# analog.net
KiCad netlist of a schematic drawn in EAGLE
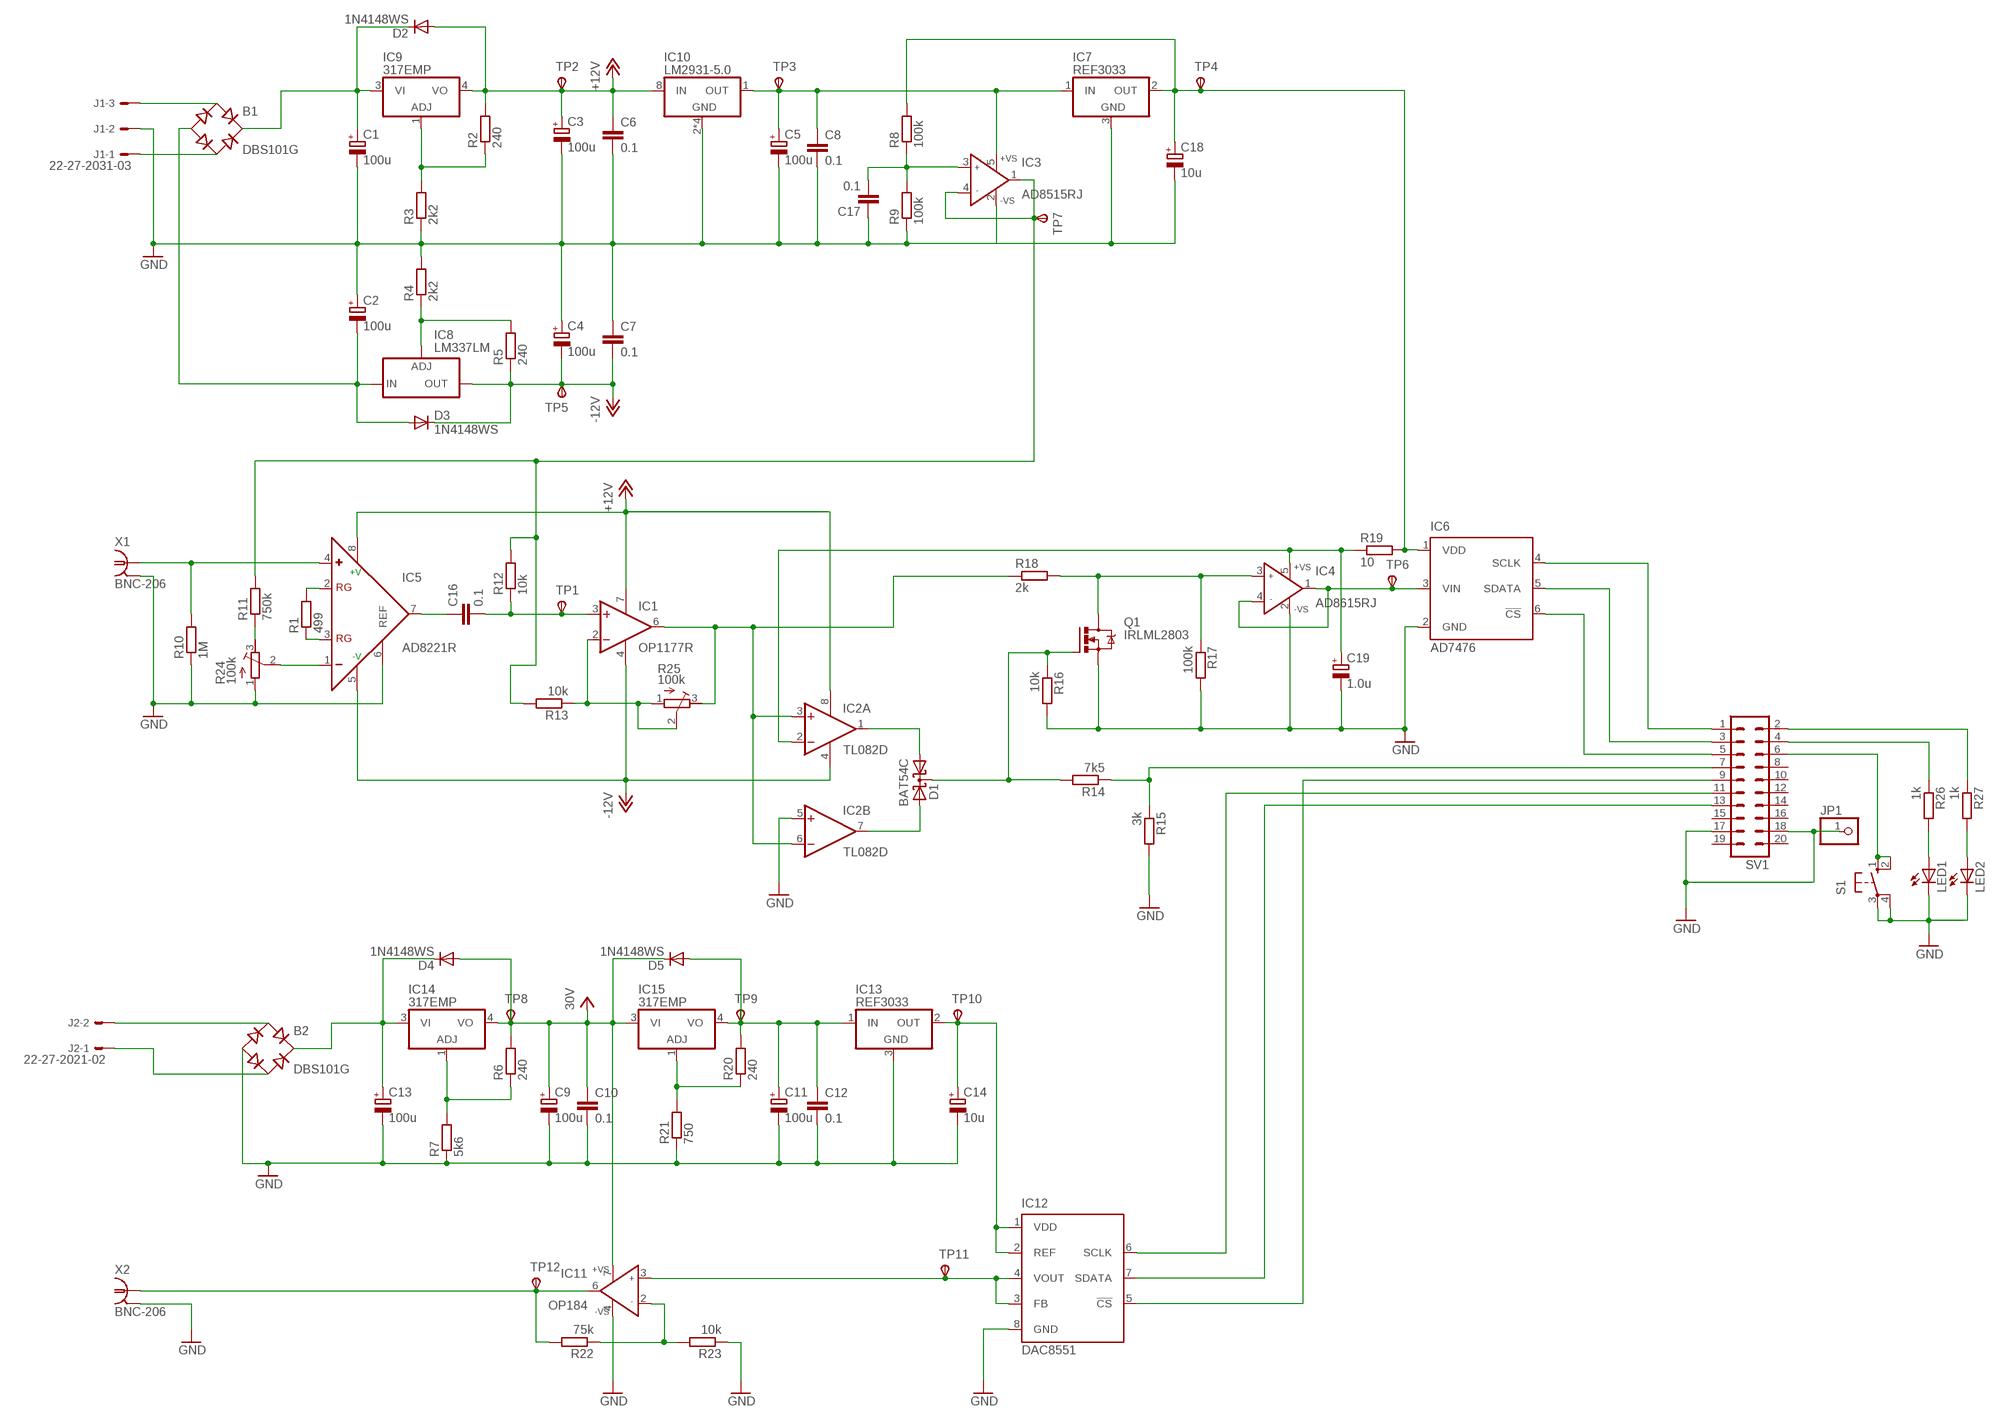
[diagram p0: schematic, sheet 1]

(export (version "E")
  (design (tool "Eeschema 10.0.6"))
  (components
    (comp (ref "B1")
      (value "DBS101G")
      (footprint "eagle-import:DBS")
      (libsource (lib "eagle-import") (part "DB?GS101"))
    )
    (comp (ref "B2")
      (value "DBS101G")
      (footprint "eagle-import:DBS")
      (libsource (lib "eagle-import") (part "DB?GS101"))
    )
    (comp (ref "C1")
      (value "100u")
      (footprint "eagle-import:E3,5-8")
      (libsource (lib "eagle-import") (part "CPOL-EUE3.5-8"))
    )
    (comp (ref "C2")
      (value "100u")
      (footprint "eagle-import:E3,5-8")
      (libsource (lib "eagle-import") (part "CPOL-EUE3.5-8"))
    )
    (comp (ref "C3")
      (value "100u")
      (footprint "eagle-import:E2,5-6")
      (libsource (lib "eagle-import") (part "CPOL-EUE2.5-6"))
    )
    (comp (ref "C4")
      (value "100u")
      (footprint "eagle-import:E2,5-6")
      (libsource (lib "eagle-import") (part "CPOL-EUE2.5-6"))
    )
    (comp (ref "C5")
      (value "100u")
      (footprint "eagle-import:E2,5-5")
      (libsource (lib "eagle-import") (part "CPOL-EUE2.5-5"))
    )
    (comp (ref "C6")
      (value "0.1")
      (footprint "eagle-import:C0805K")
      (libsource (lib "eagle-import") (part "C-EUC0805K"))
    )
    (comp (ref "C7")
      (value "0.1")
      (footprint "eagle-import:C0805K")
      (libsource (lib "eagle-import") (part "C-EUC0805K"))
    )
    (comp (ref "C8")
      (value "0.1")
      (footprint "eagle-import:C0603")
      (libsource (lib "eagle-import") (part "C-EUC0603"))
    )
    (comp (ref "C9")
      (value "100u")
      (footprint "eagle-import:E2,5-6")
      (libsource (lib "eagle-import") (part "CPOL-EUE2.5-6"))
    )
    (comp (ref "C10")
      (value "0.1")
      (footprint "eagle-import:C0805K")
      (libsource (lib "eagle-import") (part "C-EUC0805K"))
    )
    (comp (ref "C11")
      (value "100u")
      (footprint "eagle-import:E2,5-5")
      (libsource (lib "eagle-import") (part "CPOL-EUE2.5-5"))
    )
    (comp (ref "C12")
      (value "0.1")
      (footprint "eagle-import:C0603")
      (libsource (lib "eagle-import") (part "C-EUC0603"))
    )
    (comp (ref "C13")
      (value "100u")
      (footprint "eagle-import:E3,5-8")
      (libsource (lib "eagle-import") (part "CPOL-EUE3.5-8"))
    )
    (comp (ref "C14")
      (value "10u")
      (footprint "eagle-import:SMC_A")
      (libsource (lib "eagle-import") (part "CPOL-EUSMCA"))
    )
    (comp (ref "C16")
      (value "0.1")
      (footprint "eagle-import:C0603")
      (libsource (lib "eagle-import") (part "C-EUC0603"))
    )
    (comp (ref "C17")
      (value "0.1")
      (footprint "eagle-import:C0603")
      (libsource (lib "eagle-import") (part "C-EUC0603"))
    )
    (comp (ref "C18")
      (value "10u")
      (footprint "eagle-import:SMC_A")
      (libsource (lib "eagle-import") (part "CPOL-EUSMCA"))
    )
    (comp (ref "C19")
      (value "1.0u")
      (footprint "eagle-import:SMC_A")
      (libsource (lib "eagle-import") (part "CPOL-EUSMCA"))
    )
    (comp (ref "D1")
      (value "BAT54C")
      (footprint "eagle-import:SOT23")
      (libsource (lib "eagle-import") (part "BAT54C"))
    )
    (comp (ref "D2")
      (value "1N4148WS")
      (footprint "eagle-import:SOD323")
      (libsource (lib "eagle-import") (part "1N4148WS"))
    )
    (comp (ref "D3")
      (value "1N4148WS")
      (footprint "eagle-import:SOD323")
      (libsource (lib "eagle-import") (part "1N4148WS"))
    )
    (comp (ref "D4")
      (value "1N4148WS")
      (footprint "eagle-import:SOD323")
      (libsource (lib "eagle-import") (part "1N4148WS"))
    )
    (comp (ref "D5")
      (value "1N4148WS")
      (footprint "eagle-import:SOD323")
      (libsource (lib "eagle-import") (part "1N4148WS"))
    )
    (comp (ref "IC1")
      (value "OP1177R")
      (footprint "eagle-import:SOIC8")
      (libsource (lib "eagle-import") (part "OP1177R"))
    )
    (comp (ref "IC2")
      (value "TL082D")
      (footprint "eagle-import:SO08")
      (libsource (lib "eagle-import") (part "TL082D"))
    )
    (comp (ref "IC3")
      (value "AD8515RJ")
      (footprint "eagle-import:SOT23-5")
      (fields (field (name "MF") "Analog Devices") (field (name "MPN") "AD8515ARTZ-REEL7"))
      (libsource (lib "eagle-import") (part "AD8515RJ"))
    )
    (comp (ref "IC4")
      (value "AD8615RJ")
      (footprint "eagle-import:SOT23-5")
      (fields (field (name "MF") "ALTERA CORPORATION") (field (name "MPN") "AD8541ARTZ-REEL7"))
      (libsource (lib "eagle-import") (part "AD8615RJ"))
    )
    (comp (ref "IC5")
      (value "AD8221R")
      (footprint "eagle-import:SO8@1")
      (fields (field (name "MPN") "AD8221"))
      (libsource (lib "eagle-import") (part "AD8221R"))
    )
    (comp (ref "IC6")
      (value "AD7476")
      (footprint "eagle-import:SOT23-6")
      (libsource (lib "eagle-import") (part "AD7476"))
    )
    (comp (ref "IC7")
      (value "REF3033")
      (footprint "eagle-import:SOT23")
      (libsource (lib "eagle-import") (part "REF3033"))
    )
    (comp (ref "IC8")
      (value "LM337LM")
      (footprint "eagle-import:SO8")
      (libsource (lib "eagle-import") (part "LM337LM"))
    )
    (comp (ref "IC9")
      (value "317EMP")
      (footprint "eagle-import:SOT223")
      (libsource (lib "eagle-import") (part "317EMP"))
    )
    (comp (ref "IC10")
      (value "LM2931-5.0")
      (footprint "eagle-import:SO8")
      (libsource (lib "eagle-import") (part "LM2931-5.0"))
    )
    (comp (ref "IC11")
      (value "OP184")
      (footprint "eagle-import:SO8")
      (libsource (lib "eagle-import") (part "OP184"))
    )
    (comp (ref "IC12")
      (value "DAC8551")
      (footprint "eagle-import:MSOP8")
      (libsource (lib "eagle-import") (part "DAC8551"))
    )
    (comp (ref "IC13")
      (value "REF3033")
      (footprint "eagle-import:SOT23")
      (libsource (lib "eagle-import") (part "REF3033"))
    )
    (comp (ref "IC14")
      (value "317EMP")
      (footprint "eagle-import:SOT223")
      (libsource (lib "eagle-import") (part "317EMP"))
    )
    (comp (ref "IC15")
      (value "317EMP")
      (footprint "eagle-import:SOT223")
      (libsource (lib "eagle-import") (part "317EMP"))
    )
    (comp (ref "J1")
      (value "22-27-2031-03")
      (footprint "eagle-import:6410-03")
      (libsource (lib "eagle-import") (part "22-?-0327-2031"))
    )
    (comp (ref "J2")
      (value "22-27-2021-02")
      (footprint "eagle-import:6410-02")
      (libsource (lib "eagle-import") (part "22-?-0227-2021"))
    )
    (comp (ref "JP1")
      (value "PINHD-1X1")
      (footprint "eagle-import:1X01")
      (libsource (lib "eagle-import") (part "PINHD-1X1"))
    )
    (comp (ref "LED1")
      (value "LEDCHIPLED_0805")
      (footprint "eagle-import:CHIPLED_0805")
      (libsource (lib "eagle-import") (part "LEDCHIPLED_0805"))
    )
    (comp (ref "LED2")
      (value "LEDCHIPLED_0805")
      (footprint "eagle-import:CHIPLED_0805")
      (libsource (lib "eagle-import") (part "LEDCHIPLED_0805"))
    )
    (comp (ref "Q1")
      (value "IRLML2803")
      (footprint "eagle-import:SOT23")
      (libsource (lib "eagle-import") (part "IRLML2803"))
    )
    (comp (ref "R1")
      (value "499")
      (footprint "eagle-import:R0805")
      (libsource (lib "eagle-import") (part "R-EU_R0805"))
    )
    (comp (ref "R2")
      (value "240")
      (footprint "eagle-import:R0805")
      (libsource (lib "eagle-import") (part "R-EU_R0805"))
    )
    (comp (ref "R3")
      (value "2k2")
      (footprint "eagle-import:R0805")
      (libsource (lib "eagle-import") (part "R-EU_R0805"))
    )
    (comp (ref "R4")
      (value "2k2")
      (footprint "eagle-import:R0805")
      (libsource (lib "eagle-import") (part "R-EU_R0805"))
    )
    (comp (ref "R5")
      (value "240")
      (footprint "eagle-import:R0805")
      (libsource (lib "eagle-import") (part "R-EU_R0805"))
    )
    (comp (ref "R6")
      (value "240")
      (footprint "eagle-import:R0805")
      (libsource (lib "eagle-import") (part "R-EU_R0805"))
    )
    (comp (ref "R7")
      (value "5k6")
      (footprint "eagle-import:R0805")
      (libsource (lib "eagle-import") (part "R-EU_R0805"))
    )
    (comp (ref "R8")
      (value "100k")
      (footprint "eagle-import:R0603")
      (libsource (lib "eagle-import") (part "R-EU_R0603"))
    )
    (comp (ref "R9")
      (value "100k")
      (footprint "eagle-import:R0603")
      (libsource (lib "eagle-import") (part "R-EU_R0603"))
    )
    (comp (ref "R10")
      (value "1M")
      (footprint "eagle-import:R0603")
      (libsource (lib "eagle-import") (part "R-EU_R0603"))
    )
    (comp (ref "R11")
      (value "750k")
      (footprint "eagle-import:R0603")
      (libsource (lib "eagle-import") (part "R-EU_R0603"))
    )
    (comp (ref "R12")
      (value "10k")
      (footprint "eagle-import:R0603")
      (libsource (lib "eagle-import") (part "R-EU_R0603"))
    )
    (comp (ref "R13")
      (value "10k")
      (footprint "eagle-import:R0603")
      (libsource (lib "eagle-import") (part "R-EU_R0603"))
    )
    (comp (ref "R14")
      (value "7k5")
      (footprint "eagle-import:R0603")
      (libsource (lib "eagle-import") (part "R-EU_R0603"))
    )
    (comp (ref "R15")
      (value "3k")
      (footprint "eagle-import:R0603")
      (libsource (lib "eagle-import") (part "R-EU_R0603"))
    )
    (comp (ref "R16")
      (value "10k")
      (footprint "eagle-import:R0603")
      (libsource (lib "eagle-import") (part "R-EU_R0603"))
    )
    (comp (ref "R17")
      (value "100k")
      (footprint "eagle-import:R0603")
      (libsource (lib "eagle-import") (part "R-EU_R0603"))
    )
    (comp (ref "R18")
      (value "2k")
      (footprint "eagle-import:R0603")
      (libsource (lib "eagle-import") (part "R-EU_R0603"))
    )
    (comp (ref "R19")
      (value "10")
      (footprint "eagle-import:R0603")
      (libsource (lib "eagle-import") (part "R-EU_R0603"))
    )
    (comp (ref "R20")
      (value "240")
      (footprint "eagle-import:R0603")
      (libsource (lib "eagle-import") (part "R-EU_R0603"))
    )
    (comp (ref "R21")
      (value "750")
      (footprint "eagle-import:R0603")
      (libsource (lib "eagle-import") (part "R-EU_R0603"))
    )
    (comp (ref "R22")
      (value "75k")
      (footprint "eagle-import:R0603")
      (libsource (lib "eagle-import") (part "R-EU_R0603"))
    )
    (comp (ref "R23")
      (value "10k")
      (footprint "eagle-import:R0603")
      (libsource (lib "eagle-import") (part "R-EU_R0603"))
    )
    (comp (ref "R24")
      (value "100k")
      (footprint "eagle-import:RTRIM3296W")
      (libsource (lib "eagle-import") (part "R-TRIMM3296W"))
    )
    (comp (ref "R25")
      (value "100k")
      (footprint "eagle-import:RTRIM3296W")
      (libsource (lib "eagle-import") (part "R-TRIMM3296W"))
    )
    (comp (ref "R26")
      (value "1k")
      (footprint "eagle-import:R0603")
      (libsource (lib "eagle-import") (part "R-EU_R0603"))
    )
    (comp (ref "R27")
      (value "1k")
      (footprint "eagle-import:R0603")
      (libsource (lib "eagle-import") (part "R-EU_R0603"))
    )
    (comp (ref "S1")
      (value "10-XX")
      (footprint "eagle-import:B3F-10XX")
      (fields (field (name "MPN") "B3F-1000"))
      (libsource (lib "eagle-import") (part "10-XX"))
    )
    (comp (ref "SV1")
      (value "MA10-2W")
      (footprint "eagle-import:MA10-2W")
      (libsource (lib "eagle-import") (part "MA10-2W"))
    )
    (comp (ref "TP1")
      (value "TPSB2,54")
      (footprint "eagle-import:B2,54")
      (libsource (lib "eagle-import") (part "TPSB2,54"))
    )
    (comp (ref "TP2")
      (value "TPSB2,54")
      (footprint "eagle-import:B2,54")
      (libsource (lib "eagle-import") (part "TPSB2,54"))
    )
    (comp (ref "TP3")
      (value "TPSB2,54")
      (footprint "eagle-import:B2,54")
      (libsource (lib "eagle-import") (part "TPSB2,54"))
    )
    (comp (ref "TP4")
      (value "TPSB2,54")
      (footprint "eagle-import:B2,54")
      (libsource (lib "eagle-import") (part "TPSB2,54"))
    )
    (comp (ref "TP5")
      (value "TPSB2,54")
      (footprint "eagle-import:B2,54")
      (libsource (lib "eagle-import") (part "TPSB2,54"))
    )
    (comp (ref "TP6")
      (value "TPSB2,54")
      (footprint "eagle-import:B2,54")
      (libsource (lib "eagle-import") (part "TPSB2,54"))
    )
    (comp (ref "TP7")
      (value "TPSB2,54")
      (footprint "eagle-import:B2,54")
      (libsource (lib "eagle-import") (part "TPSB2,54"))
    )
    (comp (ref "TP8")
      (value "TPSB2,54")
      (footprint "eagle-import:B2,54")
      (libsource (lib "eagle-import") (part "TPSB2,54"))
    )
    (comp (ref "TP9")
      (value "TPSB2,54")
      (footprint "eagle-import:B2,54")
      (libsource (lib "eagle-import") (part "TPSB2,54"))
    )
    (comp (ref "TP10")
      (value "TPSB2,54")
      (footprint "eagle-import:B2,54")
      (libsource (lib "eagle-import") (part "TPSB2,54"))
    )
    (comp (ref "TP11")
      (value "TPSB2,54")
      (footprint "eagle-import:B2,54")
      (libsource (lib "eagle-import") (part "TPSB2,54"))
    )
    (comp (ref "TP12")
      (value "TPSB2,54")
      (footprint "eagle-import:B2,54")
      (libsource (lib "eagle-import") (part "TPSB2,54"))
    )
    (comp (ref "X1")
      (value "BNC-206")
      (footprint "eagle-import:AMP_227161")
      (fields (field (name "MF") "TYCO ELECTRONICS") (field (name "MPN") "1-227161"))
      (libsource (lib "eagle-import") (part "?2271611--0"))
    )
    (comp (ref "X2")
      (value "BNC-206")
      (footprint "eagle-import:AMP_227161")
      (fields (field (name "MF") "TYCO ELECTRONICS") (field (name "MPN") "1-227161"))
      (libsource (lib "eagle-import") (part "?2271611--0"))
    )
  )
  (nets
    (net (code "1") (name "+12V") (class "Default")
      (node (ref "C3") (pin "+") (pinfunction "+_+") (pintype "passive"))
      (node (ref "C6") (pin "1") (pinfunction "1_1") (pintype "passive"))
      (node (ref "D2") (pin "2") (pinfunction "A_2") (pintype "passive"))
      (node (ref "IC1") (pin "7") (pinfunction "V+_7") (pintype "power_in"))
      (node (ref "IC10") (pin "8") (pinfunction "IN_8") (pintype "input"))
      (node (ref "IC2") (pin "8") (pinfunction "V+_8") (pintype "power_in"))
      (node (ref "IC5") (pin "8") (pinfunction "+V_8") (pintype "power_in"))
      (node (ref "IC9") (pin "4") (pinfunction "VO_4") (pintype "passive"))
      (node (ref "R2") (pin "2") (pinfunction "2_2") (pintype "passive"))
      (node (ref "TP2") (pin "TP") (pinfunction "PP_TP") (pintype "input"))
    )
    (net (code "2") (name "-12V") (class "Default")
      (node (ref "C4") (pin "-") (pinfunction "-_-") (pintype "passive"))
      (node (ref "C7") (pin "2") (pinfunction "2_2") (pintype "passive"))
      (node (ref "D3") (pin "1") (pinfunction "C_1") (pintype "passive"))
      (node (ref "IC1") (pin "4") (pinfunction "V-_4") (pintype "power_in"))
      (node (ref "IC2") (pin "4") (pinfunction "V-_4") (pintype "power_in"))
      (node (ref "IC5") (pin "5") (pinfunction "-V_5") (pintype "power_in"))
      (node (ref "IC8") (pin "1") (pinfunction "OUT_1") (pintype "passive"))
      (node (ref "R5") (pin "1") (pinfunction "1_1") (pintype "passive"))
      (node (ref "TP5") (pin "TP") (pinfunction "PP_TP") (pintype "input"))
    )
    (net (code "3") (name "30V") (class "Default")
      (node (ref "C10") (pin "1") (pinfunction "1_1") (pintype "passive"))
      (node (ref "C9") (pin "+") (pinfunction "+_+") (pintype "passive"))
      (node (ref "D4") (pin "2") (pinfunction "A_2") (pintype "passive"))
      (node (ref "D5") (pin "1") (pinfunction "C_1") (pintype "passive"))
      (node (ref "IC11") (pin "7") (pinfunction "+VS_7") (pintype "input"))
      (node (ref "IC14") (pin "4") (pinfunction "VO_4") (pintype "passive"))
      (node (ref "IC15") (pin "3") (pinfunction "VI_3") (pintype "input"))
      (node (ref "R6") (pin "2") (pinfunction "2_2") (pintype "passive"))
      (node (ref "TP8") (pin "TP") (pinfunction "PP_TP") (pintype "input"))
    )
    (net (code "4") (name "GND") (class "Default")
      (node (ref "B2") (pin "-") (pinfunction "-_-") (pintype "passive"))
      (node (ref "C1") (pin "-") (pinfunction "-_-") (pintype "passive"))
      (node (ref "C10") (pin "2") (pinfunction "2_2") (pintype "passive"))
      (node (ref "C11") (pin "-") (pinfunction "-_-") (pintype "passive"))
      (node (ref "C12") (pin "2") (pinfunction "2_2") (pintype "passive"))
      (node (ref "C13") (pin "-") (pinfunction "-_-") (pintype "passive"))
      (node (ref "C14") (pin "-") (pinfunction "-_-") (pintype "passive"))
      (node (ref "C17") (pin "1") (pinfunction "1_1") (pintype "passive"))
      (node (ref "C18") (pin "-") (pinfunction "-_-") (pintype "passive"))
      (node (ref "C19") (pin "-") (pinfunction "-_-") (pintype "passive"))
      (node (ref "C2") (pin "+") (pinfunction "+_+") (pintype "passive"))
      (node (ref "C3") (pin "-") (pinfunction "-_-") (pintype "passive"))
      (node (ref "C4") (pin "+") (pinfunction "+_+") (pintype "passive"))
      (node (ref "C5") (pin "-") (pinfunction "-_-") (pintype "passive"))
      (node (ref "C6") (pin "2") (pinfunction "2_2") (pintype "passive"))
      (node (ref "C7") (pin "1") (pinfunction "1_1") (pintype "passive"))
      (node (ref "C8") (pin "2") (pinfunction "2_2") (pintype "passive"))
      (node (ref "C9") (pin "-") (pinfunction "-_-") (pintype "passive"))
      (node (ref "IC10") (pin "2") (pinfunction "GND_2") (pintype "input"))
      (node (ref "IC10") (pin "3") (pinfunction "GND_3") (pintype "input"))
      (node (ref "IC10") (pin "6") (pinfunction "GND_6") (pintype "input"))
      (node (ref "IC10") (pin "7") (pinfunction "GND_7") (pintype "input"))
      (node (ref "IC11") (pin "4") (pinfunction "-VS_4") (pintype "input"))
      (node (ref "IC12") (pin "8") (pinfunction "GND_8") (pintype "power_in"))
      (node (ref "IC13") (pin "3") (pinfunction "GND_3") (pintype "input"))
      (node (ref "IC2") (pin "5") (pinfunction "+IN_5") (pintype "input"))
      (node (ref "IC3") (pin "2") (pinfunction "-VS_2") (pintype "input"))
      (node (ref "IC4") (pin "2") (pinfunction "-VS_2") (pintype "input"))
      (node (ref "IC5") (pin "6") (pinfunction "REF_6") (pintype "passive"))
      (node (ref "IC6") (pin "2") (pinfunction "GND_2") (pintype "power_in"))
      (node (ref "IC7") (pin "3") (pinfunction "GND_3") (pintype "input"))
      (node (ref "J1") (pin "2") (pinfunction "S_2") (pintype "passive"))
      (node (ref "JP1") (pin "1") (pinfunction "1_1") (pintype "passive"))
      (node (ref "LED1") (pin "C") (pinfunction "C_C") (pintype "passive"))
      (node (ref "LED2") (pin "C") (pinfunction "C_C") (pintype "passive"))
      (node (ref "Q1") (pin "2") (pinfunction "S_2") (pintype "passive"))
      (node (ref "R10") (pin "1") (pinfunction "1_1") (pintype "passive"))
      (node (ref "R15") (pin "2") (pinfunction "2_2") (pintype "passive"))
      (node (ref "R16") (pin "2") (pinfunction "2_2") (pintype "passive"))
      (node (ref "R17") (pin "2") (pinfunction "2_2") (pintype "passive"))
      (node (ref "R21") (pin "1") (pinfunction "1_1") (pintype "passive"))
      (node (ref "R23") (pin "1") (pinfunction "1_1") (pintype "passive"))
      (node (ref "R24") (pin "1") (pinfunction "A_1") (pintype "passive"))
      (node (ref "R3") (pin "1") (pinfunction "1_1") (pintype "passive"))
      (node (ref "R4") (pin "2") (pinfunction "2_2") (pintype "passive"))
      (node (ref "R7") (pin "1") (pinfunction "1_1") (pintype "passive"))
      (node (ref "R9") (pin "1") (pinfunction "1_1") (pintype "passive"))
      (node (ref "S1") (pin "3") (pinfunction "P_3") (pintype "passive"))
      (node (ref "S1") (pin "4") (pinfunction "P1_4") (pintype "passive"))
      (node (ref "SV1") (pin "17") (pinfunction "17_17") (pintype "passive"))
      (node (ref "SV1") (pin "18") (pinfunction "18_18") (pintype "passive"))
      (node (ref "X1") (pin "2") (pinfunction "2_2") (pintype "passive"))
      (node (ref "X2") (pin "2") (pinfunction "2_2") (pintype "passive"))
    )
    (net (code "5") (name "Net-(D1-A1)") (class "Default")
      (node (ref "D1") (pin "1") (pinfunction "A1_1") (pintype "passive"))
      (node (ref "IC2") (pin "1") (pinfunction "OUT_1") (pintype "output"))
    )
    (net (code "6") (name "Net-(D1-A2)") (class "Default")
      (node (ref "D1") (pin "2") (pinfunction "A2_2") (pintype "passive"))
      (node (ref "IC2") (pin "7") (pinfunction "OUT_7") (pintype "output"))
    )
    (net (code "7") (name "Net-(D1-CC)") (class "Default")
      (node (ref "D1") (pin "3") (pinfunction "CC_3") (pintype "passive"))
      (node (ref "Q1") (pin "1") (pinfunction "G_1") (pintype "passive"))
      (node (ref "R14") (pin "2") (pinfunction "2_2") (pintype "passive"))
      (node (ref "R16") (pin "1") (pinfunction "1_1") (pintype "passive"))
    )
    (net (code "8") (name "Net-(D2-C)") (class "Default")
      (node (ref "B1") (pin "+") (pinfunction "+_+") (pintype "passive"))
      (node (ref "C1") (pin "+") (pinfunction "+_+") (pintype "passive"))
      (node (ref "D2") (pin "1") (pinfunction "C_1") (pintype "passive"))
      (node (ref "IC9") (pin "3") (pinfunction "VI_3") (pintype "input"))
    )
    (net (code "9") (name "Net-(D3-A)") (class "Default")
      (node (ref "B1") (pin "-") (pinfunction "-_-") (pintype "passive"))
      (node (ref "C2") (pin "-") (pinfunction "-_-") (pintype "passive"))
      (node (ref "D3") (pin "2") (pinfunction "A_2") (pintype "passive"))
      (node (ref "IC8") (pin "2") (pinfunction "IN_2") (pintype "input"))
      (node (ref "IC8") (pin "3") (pinfunction "IN_3") (pintype "input"))
      (node (ref "IC8") (pin "6") (pinfunction "IN_6") (pintype "input"))
      (node (ref "IC8") (pin "7") (pinfunction "IN_7") (pintype "input"))
    )
    (net (code "10") (name "Net-(D4-C)") (class "Default")
      (node (ref "B2") (pin "+") (pinfunction "+_+") (pintype "passive"))
      (node (ref "C13") (pin "+") (pinfunction "+_+") (pintype "passive"))
      (node (ref "D4") (pin "1") (pinfunction "C_1") (pintype "passive"))
      (node (ref "IC14") (pin "3") (pinfunction "VI_3") (pintype "input"))
    )
    (net (code "11") (name "Net-(D5-A)") (class "Default")
      (node (ref "C11") (pin "+") (pinfunction "+_+") (pintype "passive"))
      (node (ref "C12") (pin "1") (pinfunction "1_1") (pintype "passive"))
      (node (ref "D5") (pin "2") (pinfunction "A_2") (pintype "passive"))
      (node (ref "IC13") (pin "1") (pinfunction "IN_1") (pintype "input"))
      (node (ref "IC15") (pin "4") (pinfunction "VO_4") (pintype "passive"))
      (node (ref "R20") (pin "2") (pinfunction "2_2") (pintype "passive"))
      (node (ref "TP9") (pin "TP") (pinfunction "PP_TP") (pintype "input"))
    )
    (net (code "12") (name "Net-(IC1-+IN)") (class "Default")
      (node (ref "C16") (pin "2") (pinfunction "2_2") (pintype "passive"))
      (node (ref "IC1") (pin "3") (pinfunction "+IN_3") (pintype "input"))
      (node (ref "R12") (pin "1") (pinfunction "1_1") (pintype "passive"))
      (node (ref "TP1") (pin "TP") (pinfunction "PP_TP") (pintype "input"))
    )
    (net (code "13") (name "Net-(IC1--IN)") (class "Default")
      (node (ref "IC1") (pin "2") (pinfunction "-IN_2") (pintype "input"))
      (node (ref "R13") (pin "1") (pinfunction "1_1") (pintype "passive"))
      (node (ref "R25") (pin "1") (pinfunction "A_1") (pintype "passive"))
      (node (ref "R25") (pin "2") (pinfunction "S_2") (pintype "passive"))
    )
    (net (code "14") (name "Net-(IC1-OUT)") (class "Default")
      (node (ref "IC1") (pin "6") (pinfunction "OUT_6") (pintype "output"))
      (node (ref "IC2") (pin "3") (pinfunction "+IN_3") (pintype "input"))
      (node (ref "IC2") (pin "6") (pinfunction "-IN_6") (pintype "input"))
      (node (ref "R18") (pin "1") (pinfunction "1_1") (pintype "passive"))
      (node (ref "R25") (pin "3") (pinfunction "E_3") (pintype "passive"))
    )
    (net (code "15") (name "Net-(IC2A--IN)") (class "Default")
      (node (ref "C19") (pin "+") (pinfunction "+_+") (pintype "passive"))
      (node (ref "IC2") (pin "2") (pinfunction "-IN_2") (pintype "input"))
      (node (ref "IC4") (pin "5") (pinfunction "+VS_5") (pintype "input"))
      (node (ref "R19") (pin "1") (pinfunction "1_1") (pintype "passive"))
    )
    (net (code "16") (name "Net-(IC3-IN+)") (class "Default")
      (node (ref "C17") (pin "2") (pinfunction "2_2") (pintype "passive"))
      (node (ref "IC3") (pin "3") (pinfunction "IN+_3") (pintype "input"))
      (node (ref "R8") (pin "1") (pinfunction "1_1") (pintype "passive"))
      (node (ref "R9") (pin "2") (pinfunction "2_2") (pintype "passive"))
    )
    (net (code "17") (name "Net-(IC3-IN-)") (class "Default")
      (node (ref "IC3") (pin "1") (pinfunction "OUT_1") (pintype "output"))
      (node (ref "IC3") (pin "4") (pinfunction "IN-_4") (pintype "input"))
      (node (ref "R11") (pin "2") (pinfunction "2_2") (pintype "passive"))
      (node (ref "R12") (pin "2") (pinfunction "2_2") (pintype "passive"))
      (node (ref "R13") (pin "2") (pinfunction "2_2") (pintype "passive"))
      (node (ref "TP7") (pin "TP") (pinfunction "PP_TP") (pintype "input"))
    )
    (net (code "18") (name "Net-(IC4-IN+)") (class "Default")
      (node (ref "IC4") (pin "3") (pinfunction "IN+_3") (pintype "input"))
      (node (ref "Q1") (pin "3") (pinfunction "D_3") (pintype "passive"))
      (node (ref "R17") (pin "1") (pinfunction "1_1") (pintype "passive"))
      (node (ref "R18") (pin "2") (pinfunction "2_2") (pintype "passive"))
    )
    (net (code "19") (name "Net-(IC4-IN-)") (class "Default")
      (node (ref "IC4") (pin "1") (pinfunction "OUT_1") (pintype "output"))
      (node (ref "IC4") (pin "4") (pinfunction "IN-_4") (pintype "input"))
      (node (ref "IC6") (pin "3") (pinfunction "VIN_3") (pintype "passive"))
      (node (ref "TP6") (pin "TP") (pinfunction "PP_TP") (pintype "input"))
    )
    (net (code "20") (name "Net-(IC5-+)") (class "Default")
      (node (ref "IC5") (pin "4") (pinfunction "+_4") (pintype "input"))
      (node (ref "R10") (pin "2") (pinfunction "2_2") (pintype "passive"))
      (node (ref "X1") (pin "1") (pinfunction "1_1") (pintype "passive"))
    )
    (net (code "21") (name "Net-(IC5--)") (class "Default")
      (node (ref "IC5") (pin "1") (pinfunction "-_1") (pintype "input"))
      (node (ref "R24") (pin "2") (pinfunction "S_2") (pintype "passive"))
    )
    (net (code "22") (name "Net-(IC5-OUT)") (class "Default")
      (node (ref "C16") (pin "1") (pinfunction "1_1") (pintype "passive"))
      (node (ref "IC5") (pin "7") (pinfunction "OUT_7") (pintype "output"))
    )
    (net (code "23") (name "Net-(IC5-RG-Pad2)") (class "Default")
      (node (ref "IC5") (pin "2") (pinfunction "RG_2") (pintype "passive"))
      (node (ref "R1") (pin "2") (pinfunction "2_2") (pintype "passive"))
    )
    (net (code "24") (name "Net-(IC5-RG-Pad3)") (class "Default")
      (node (ref "IC5") (pin "3") (pinfunction "RG_3") (pintype "passive"))
      (node (ref "R1") (pin "1") (pinfunction "1_1") (pintype "passive"))
    )
    (net (code "25") (name "Net-(IC6-SCLK)") (class "Default")
      (node (ref "IC6") (pin "4") (pinfunction "SCLK_4") (pintype "input"))
      (node (ref "SV1") (pin "1") (pinfunction "1_1") (pintype "passive"))
    )
    (net (code "26") (name "Net-(IC6-SDATA)") (class "Default")
      (node (ref "IC6") (pin "5") (pinfunction "SDATA_5") (pintype "input"))
      (node (ref "SV1") (pin "3") (pinfunction "3_3") (pintype "passive"))
    )
    (net (code "27") (name "Net-(IC6-VDD)") (class "Default")
      (node (ref "C18") (pin "+") (pinfunction "+_+") (pintype "passive"))
      (node (ref "IC6") (pin "1") (pinfunction "VDD_1") (pintype "power_in"))
      (node (ref "IC7") (pin "2") (pinfunction "OUT_2") (pintype "passive"))
      (node (ref "R19") (pin "2") (pinfunction "2_2") (pintype "passive"))
      (node (ref "R8") (pin "2") (pinfunction "2_2") (pintype "passive"))
      (node (ref "TP4") (pin "TP") (pinfunction "PP_TP") (pintype "input"))
    )
    (net (code "28") (name "Net-(IC6-~{CS})") (class "Default")
      (node (ref "IC6") (pin "6") (pinfunction "~{CS}_6") (pintype "input"))
      (node (ref "SV1") (pin "5") (pinfunction "5_5") (pintype "passive"))
    )
    (net (code "29") (name "Net-(IC8-ADJ)") (class "Default")
      (node (ref "IC8") (pin "4") (pinfunction "ADJ_4") (pintype "input"))
      (node (ref "R4") (pin "1") (pinfunction "1_1") (pintype "passive"))
      (node (ref "R5") (pin "2") (pinfunction "2_2") (pintype "passive"))
    )
    (net (code "30") (name "Net-(IC9-ADJ)") (class "Default")
      (node (ref "IC9") (pin "1") (pinfunction "ADJ_1") (pintype "input"))
      (node (ref "R2") (pin "1") (pinfunction "1_1") (pintype "passive"))
      (node (ref "R3") (pin "2") (pinfunction "2_2") (pintype "passive"))
    )
    (net (code "31") (name "Net-(IC10-OUT)") (class "Default")
      (node (ref "C5") (pin "+") (pinfunction "+_+") (pintype "passive"))
      (node (ref "C8") (pin "1") (pinfunction "1_1") (pintype "passive"))
      (node (ref "IC10") (pin "1") (pinfunction "OUT_1") (pintype "passive"))
      (node (ref "IC3") (pin "5") (pinfunction "+VS_5") (pintype "input"))
      (node (ref "IC7") (pin "1") (pinfunction "IN_1") (pintype "input"))
      (node (ref "TP3") (pin "TP") (pinfunction "PP_TP") (pintype "input"))
    )
    (net (code "32") (name "Net-(IC11-IN+)") (class "Default")
      (node (ref "IC11") (pin "3") (pinfunction "IN+_3") (pintype "input"))
      (node (ref "IC12") (pin "3") (pinfunction "FB_3") (pintype "passive"))
      (node (ref "IC12") (pin "4") (pinfunction "VOUT_4") (pintype "passive"))
      (node (ref "TP11") (pin "TP") (pinfunction "PP_TP") (pintype "input"))
    )
    (net (code "33") (name "Net-(IC11-IN-)") (class "Default")
      (node (ref "IC11") (pin "2") (pinfunction "IN-_2") (pintype "input"))
      (node (ref "R22") (pin "1") (pinfunction "1_1") (pintype "passive"))
      (node (ref "R23") (pin "2") (pinfunction "2_2") (pintype "passive"))
    )
    (net (code "34") (name "Net-(IC11-OUT)") (class "Default")
      (node (ref "IC11") (pin "6") (pinfunction "OUT_6") (pintype "output"))
      (node (ref "R22") (pin "2") (pinfunction "2_2") (pintype "passive"))
      (node (ref "TP12") (pin "TP") (pinfunction "PP_TP") (pintype "input"))
      (node (ref "X2") (pin "1") (pinfunction "1_1") (pintype "passive"))
    )
    (net (code "35") (name "Net-(IC12-REF)") (class "Default")
      (node (ref "C14") (pin "+") (pinfunction "+_+") (pintype "passive"))
      (node (ref "IC12") (pin "1") (pinfunction "VDD_1") (pintype "power_in"))
      (node (ref "IC12") (pin "2") (pinfunction "REF_2") (pintype "power_in"))
      (node (ref "IC13") (pin "2") (pinfunction "OUT_2") (pintype "passive"))
      (node (ref "TP10") (pin "TP") (pinfunction "PP_TP") (pintype "input"))
    )
    (net (code "36") (name "Net-(IC12-SCLK)") (class "Default")
      (node (ref "IC12") (pin "6") (pinfunction "SCLK_6") (pintype "input"))
      (node (ref "SV1") (pin "11") (pinfunction "11_11") (pintype "passive"))
    )
    (net (code "37") (name "Net-(IC12-SDATA)") (class "Default")
      (node (ref "IC12") (pin "7") (pinfunction "SDATA_7") (pintype "input"))
      (node (ref "SV1") (pin "13") (pinfunction "13_13") (pintype "passive"))
    )
    (net (code "38") (name "Net-(IC12-~{CS})") (class "Default")
      (node (ref "IC12") (pin "5") (pinfunction "~{CS}_5") (pintype "input"))
      (node (ref "SV1") (pin "9") (pinfunction "9_9") (pintype "passive"))
    )
    (net (code "39") (name "Net-(IC14-ADJ)") (class "Default")
      (node (ref "IC14") (pin "1") (pinfunction "ADJ_1") (pintype "input"))
      (node (ref "R6") (pin "1") (pinfunction "1_1") (pintype "passive"))
      (node (ref "R7") (pin "2") (pinfunction "2_2") (pintype "passive"))
    )
    (net (code "40") (name "Net-(IC15-ADJ)") (class "Default")
      (node (ref "IC15") (pin "1") (pinfunction "ADJ_1") (pintype "input"))
      (node (ref "R20") (pin "1") (pinfunction "1_1") (pintype "passive"))
      (node (ref "R21") (pin "2") (pinfunction "2_2") (pintype "passive"))
    )
    (net (code "41") (name "Net-(J1A-S)") (class "Default")
      (node (ref "B1") (pin "AC2") (pinfunction "AC2_AC2") (pintype "passive"))
      (node (ref "J1") (pin "1") (pinfunction "S_1") (pintype "passive"))
    )
    (net (code "42") (name "Net-(J1C-S)") (class "Default")
      (node (ref "B1") (pin "AC1") (pinfunction "AC1_AC1") (pintype "passive"))
      (node (ref "J1") (pin "3") (pinfunction "S_3") (pintype "passive"))
    )
    (net (code "43") (name "Net-(J2A-S)") (class "Default")
      (node (ref "B2") (pin "AC2") (pinfunction "AC2_AC2") (pintype "passive"))
      (node (ref "J2") (pin "1") (pinfunction "S_1") (pintype "passive"))
    )
    (net (code "44") (name "Net-(J2B-S)") (class "Default")
      (node (ref "B2") (pin "AC1") (pinfunction "AC1_AC1") (pintype "passive"))
      (node (ref "J2") (pin "2") (pinfunction "S_2") (pintype "passive"))
    )
    (net (code "45") (name "Net-(LED1-PadA)") (class "Default")
      (node (ref "LED1") (pin "A") (pinfunction "A_A") (pintype "passive"))
      (node (ref "R26") (pin "2") (pinfunction "2_2") (pintype "passive"))
    )
    (net (code "46") (name "Net-(LED2-PadA)") (class "Default")
      (node (ref "LED2") (pin "A") (pinfunction "A_A") (pintype "passive"))
      (node (ref "R27") (pin "2") (pinfunction "2_2") (pintype "passive"))
    )
    (net (code "47") (name "Net-(R14-Pad1)") (class "Default")
      (node (ref "R14") (pin "1") (pinfunction "1_1") (pintype "passive"))
      (node (ref "R15") (pin "1") (pinfunction "1_1") (pintype "passive"))
      (node (ref "SV1") (pin "7") (pinfunction "7_7") (pintype "passive"))
    )
    (net (code "48") (name "Net-(R24-E)") (class "Default")
      (node (ref "R11") (pin "1") (pinfunction "1_1") (pintype "passive"))
      (node (ref "R24") (pin "3") (pinfunction "E_3") (pintype "passive"))
    )
    (net (code "49") (name "Net-(R26-Pad1)") (class "Default")
      (node (ref "R26") (pin "1") (pinfunction "1_1") (pintype "passive"))
      (node (ref "SV1") (pin "4") (pinfunction "4_4") (pintype "passive"))
    )
    (net (code "50") (name "Net-(R27-Pad1)") (class "Default")
      (node (ref "R27") (pin "1") (pinfunction "1_1") (pintype "passive"))
      (node (ref "SV1") (pin "2") (pinfunction "2_2") (pintype "passive"))
    )
    (net (code "51") (name "Net-(S1-S)") (class "Default")
      (node (ref "S1") (pin "1") (pinfunction "S_1") (pintype "passive"))
      (node (ref "S1") (pin "2") (pinfunction "S1_2") (pintype "passive"))
      (node (ref "SV1") (pin "6") (pinfunction "6_6") (pintype "passive"))
    )
    (net (code "52") (name "unconnected-(SV1-Pad8)") (class "Default")
      (node (ref "SV1") (pin "8") (pinfunction "8_8") (pintype "passive"))
    )
    (net (code "53") (name "unconnected-(SV1-Pad10)") (class "Default")
      (node (ref "SV1") (pin "10") (pinfunction "10_10") (pintype "passive"))
    )
    (net (code "54") (name "unconnected-(SV1-Pad12)") (class "Default")
      (node (ref "SV1") (pin "12") (pinfunction "12_12") (pintype "passive"))
    )
    (net (code "55") (name "unconnected-(SV1-Pad14)") (class "Default")
      (node (ref "SV1") (pin "14") (pinfunction "14_14") (pintype "passive"))
    )
    (net (code "56") (name "unconnected-(SV1-Pad15)") (class "Default")
      (node (ref "SV1") (pin "15") (pinfunction "15_15") (pintype "passive"))
    )
    (net (code "57") (name "unconnected-(SV1-Pad16)") (class "Default")
      (node (ref "SV1") (pin "16") (pinfunction "16_16") (pintype "passive"))
    )
    (net (code "58") (name "unconnected-(SV1-Pad19)") (class "Default")
      (node (ref "SV1") (pin "19") (pinfunction "19_19") (pintype "passive"))
    )
    (net (code "59") (name "unconnected-(SV1-Pad20)") (class "Default")
      (node (ref "SV1") (pin "20") (pinfunction "20_20") (pintype "passive"))
    )
  )
)
